# Temperature.net
KiCad netlist of a schematic drawn in Altium Designer
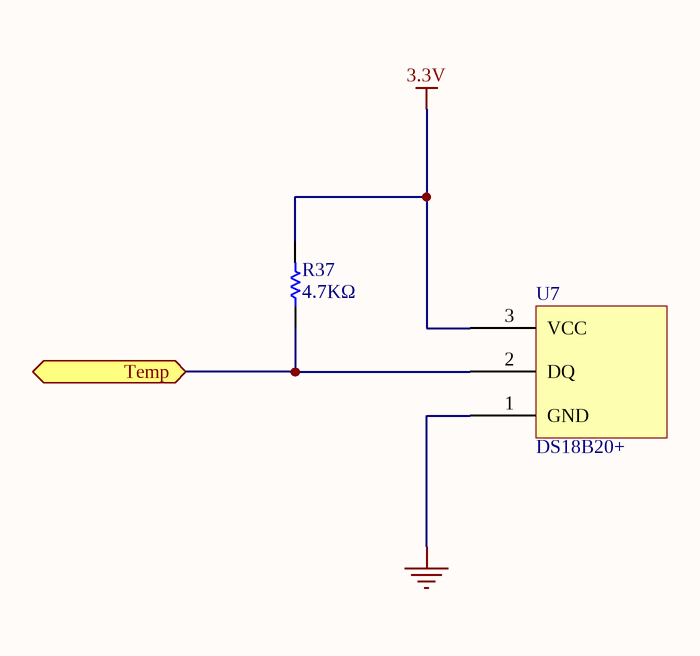
[diagram p0: Temperature.SchDoc]

(export (version "E")
  (design (tool "Eeschema 10.0.6"))
  (components
    (comp (ref "R37")
      (value "4.7KΩ")
      (footprint "R0603")
      (description "Resistor")
      (fields (field (name "MANUFACTURER") "MULTICOMP") (field (name "PUBLISHER") "Altium Limited"))
      (libsource (lib "Miscellaneous Devices") (part "Res1"))
    )
    (comp (ref "U7")
      (value "DS18B20+")
      (footprint "DS18B20+")
      (description "Temp")
      (fields (field (name "MANUFACTURER") "MAXIM INTEGRATED PRODUCTS"))
      (libsource (lib "Electroplant") (part "DS18B20+"))
    )
  )
  (nets
    (net (code "1") (name "/Temp") (class "Default")
      (node (ref "R37") (pin "1") (pinfunction "1_1") (pintype "passive"))
      (node (ref "U7") (pin "2") (pinfunction "DQ_2") (pintype "passive"))
    )
    (net (code "2") (name "3.3V") (class "Default")
      (node (ref "R37") (pin "2") (pinfunction "2_2") (pintype "passive"))
      (node (ref "U7") (pin "3") (pinfunction "VCC_3") (pintype "passive"))
    )
    (net (code "3") (name "GND") (class "Default")
      (node (ref "U7") (pin "1") (pinfunction "GND_1") (pintype "passive"))
    )
  )
)
